# core_3.net
KiCad netlist of a schematic drawn in EAGLE
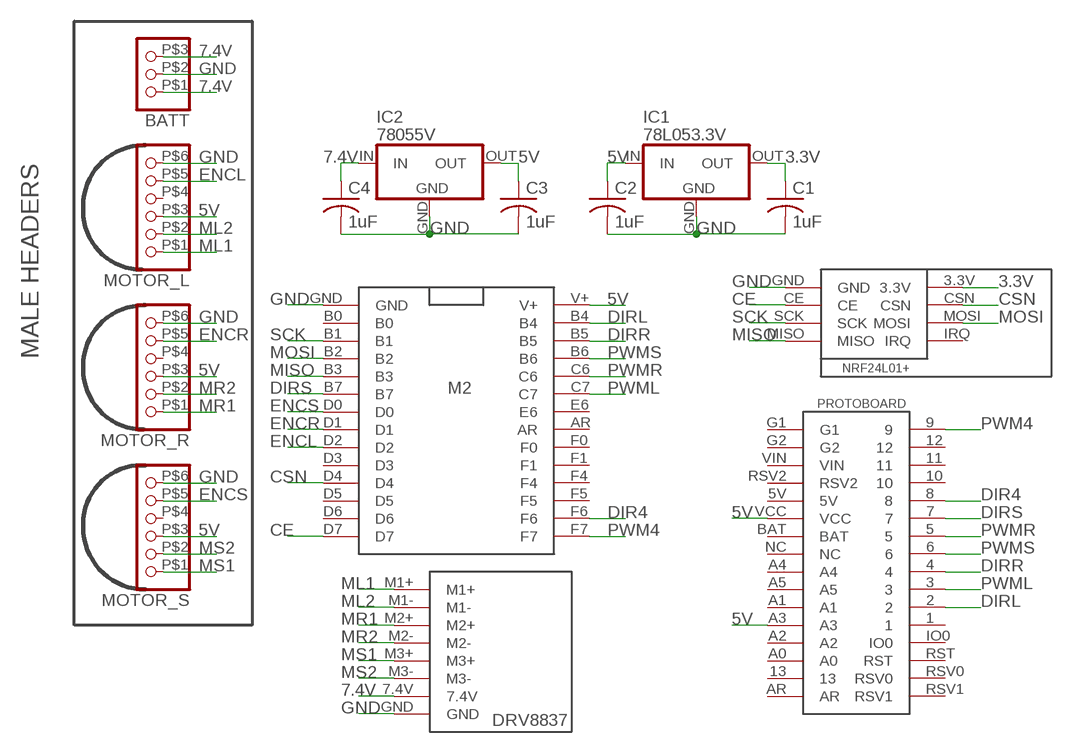
[diagram p0: schematic, sheet 1]

(export (version "E")
  (design (tool "Eeschema 10.0.6"))
  (components
    (comp (ref "BATT")
      (value "PINHD-1X3SMD")
      (footprint "eagle-import:1X3_90SMD")
      (libsource (lib "eagle-import") (part "PINHD-1X3SMD"))
    )
    (comp (ref "C1")
      (value "1uF")
      (footprint "eagle-import:C025-030X050")
      (libsource (lib "eagle-import") (part "C-US025-030X050"))
    )
    (comp (ref "C2")
      (value "1uF")
      (footprint "eagle-import:C025-030X050")
      (libsource (lib "eagle-import") (part "C-US025-030X050"))
    )
    (comp (ref "C3")
      (value "1uF")
      (footprint "eagle-import:C025-030X050")
      (libsource (lib "eagle-import") (part "C-US025-030X050"))
    )
    (comp (ref "C4")
      (value "1uF")
      (footprint "eagle-import:C025-030X050")
      (libsource (lib "eagle-import") (part "C-US025-030X050"))
    )
    (comp (ref "IC1")
      (value "78L053.3V")
      (footprint "eagle-import:TO92")
      (libsource (lib "eagle-import") (part "783.3VL05"))
    )
    (comp (ref "IC2")
      (value "78055V")
      (footprint "eagle-import:TO220H")
      (libsource (lib "eagle-import") (part "785V05"))
    )
    (comp (ref "MOTOR_L")
      (value "PINHD-1X6SMD")
      (footprint "eagle-import:1X6_90SMD")
      (libsource (lib "eagle-import") (part "PINHD-1X6SMD"))
    )
    (comp (ref "MOTOR_R")
      (value "PINHD-1X6SMD")
      (footprint "eagle-import:1X6_90SMD")
      (libsource (lib "eagle-import") (part "PINHD-1X6SMD"))
    )
    (comp (ref "MOTOR_S")
      (value "PINHD-1X6SMD")
      (footprint "eagle-import:1X6_90SMD")
      (libsource (lib "eagle-import") (part "PINHD-1X6SMD"))
    )
    (comp (ref "U$1")
      (value "NRF24L01")
      (footprint "eagle-import:NRF24L01")
      (libsource (lib "eagle-import") (part "NRF24L01"))
    )
    (comp (ref "U$2") (value "M2") (footprint "eagle-import:M2") (libsource (lib "eagle-import") (part "M2")))
    (comp (ref "U$3")
      (value "PROTOBOARDSMD")
      (footprint "eagle-import:PROTOSMD")
      (libsource (lib "eagle-import") (part "PROTOBOARDSMD"))
    )
    (comp (ref "U$4")
      (value "DRV8837")
      (footprint "eagle-import:DRV8837")
      (libsource (lib "eagle-import") (part "DRV8837"))
    )
  )
  (nets
    (net (code "1") (name "/3.3V") (class "Default")
      (node (ref "C1") (pin "1") (pinfunction "1_1") (pintype "passive"))
      (node (ref "IC1") (pin "OUT") (pinfunction "OUT_OUT") (pintype "passive"))
      (node (ref "U$1") (pin "3.3V") (pinfunction "3.3V_3.3V") (pintype "bidirectional"))
    )
    (net (code "2") (name "/5V") (class "Default")
      (node (ref "C2") (pin "1") (pinfunction "1_1") (pintype "passive"))
      (node (ref "C3") (pin "1") (pinfunction "1_1") (pintype "passive"))
      (node (ref "IC1") (pin "IN") (pinfunction "IN_IN") (pintype "input"))
      (node (ref "IC2") (pin "OUT") (pinfunction "OUT_OUT") (pintype "passive"))
      (node (ref "MOTOR_L") (pin "P$3") (pinfunction "3_P$3") (pintype "passive"))
      (node (ref "MOTOR_R") (pin "P$3") (pinfunction "3_P$3") (pintype "passive"))
      (node (ref "MOTOR_S") (pin "P$3") (pinfunction "3_P$3") (pintype "passive"))
      (node (ref "U$2") (pin "V+") (pinfunction "V+_V+") (pintype "bidirectional"))
      (node (ref "U$3") (pin "A3") (pinfunction "A3_A3") (pintype "bidirectional"))
      (node (ref "U$3") (pin "VCC") (pinfunction "VCC_VCC") (pintype "bidirectional"))
    )
    (net (code "3") (name "/7.4V") (class "Default")
      (node (ref "BATT") (pin "P$1") (pinfunction "1_P$1") (pintype "passive"))
      (node (ref "BATT") (pin "P$3") (pinfunction "3_P$3") (pintype "passive"))
      (node (ref "C4") (pin "1") (pinfunction "1_1") (pintype "passive"))
      (node (ref "IC2") (pin "IN") (pinfunction "IN_IN") (pintype "input"))
      (node (ref "U$4") (pin "7.4V") (pinfunction "7.4V_7.4V") (pintype "bidirectional"))
    )
    (net (code "4") (name "/CE") (class "Default")
      (node (ref "U$1") (pin "CE") (pinfunction "CE_CE") (pintype "bidirectional"))
      (node (ref "U$2") (pin "D7") (pinfunction "D7_D7") (pintype "bidirectional"))
    )
    (net (code "5") (name "/CSN") (class "Default")
      (node (ref "U$1") (pin "CSN") (pinfunction "CSN_CSN") (pintype "bidirectional"))
      (node (ref "U$2") (pin "D4") (pinfunction "D4_D4") (pintype "bidirectional"))
    )
    (net (code "6") (name "/DIR4") (class "Default")
      (node (ref "U$2") (pin "F6") (pinfunction "F6_F6") (pintype "bidirectional"))
      (node (ref "U$3") (pin "8") (pinfunction "8_8") (pintype "bidirectional"))
    )
    (net (code "7") (name "/DIRL") (class "Default")
      (node (ref "U$2") (pin "B4") (pinfunction "B4_B4") (pintype "bidirectional"))
      (node (ref "U$3") (pin "2") (pinfunction "2_2") (pintype "bidirectional"))
    )
    (net (code "8") (name "/DIRR") (class "Default")
      (node (ref "U$2") (pin "B5") (pinfunction "B5_B5") (pintype "bidirectional"))
      (node (ref "U$3") (pin "4") (pinfunction "4_4") (pintype "bidirectional"))
    )
    (net (code "9") (name "/DIRS") (class "Default")
      (node (ref "U$2") (pin "B7") (pinfunction "B7_B7") (pintype "bidirectional"))
      (node (ref "U$3") (pin "7") (pinfunction "7_7") (pintype "bidirectional"))
    )
    (net (code "10") (name "/ENCL") (class "Default")
      (node (ref "MOTOR_L") (pin "P$5") (pinfunction "5_P$5") (pintype "passive"))
      (node (ref "U$2") (pin "D2") (pinfunction "D2_D2") (pintype "bidirectional"))
    )
    (net (code "11") (name "/ENCR") (class "Default")
      (node (ref "MOTOR_R") (pin "P$5") (pinfunction "5_P$5") (pintype "passive"))
      (node (ref "U$2") (pin "D1") (pinfunction "D1_D1") (pintype "bidirectional"))
    )
    (net (code "12") (name "/ENCS") (class "Default")
      (node (ref "MOTOR_S") (pin "P$5") (pinfunction "5_P$5") (pintype "passive"))
      (node (ref "U$2") (pin "D0") (pinfunction "D0_D0") (pintype "bidirectional"))
    )
    (net (code "13") (name "/GND") (class "Default")
      (node (ref "BATT") (pin "P$2") (pinfunction "2_P$2") (pintype "passive"))
      (node (ref "C1") (pin "2") (pinfunction "2_2") (pintype "passive"))
      (node (ref "C2") (pin "2") (pinfunction "2_2") (pintype "passive"))
      (node (ref "C3") (pin "2") (pinfunction "2_2") (pintype "passive"))
      (node (ref "C4") (pin "2") (pinfunction "2_2") (pintype "passive"))
      (node (ref "IC1") (pin "GND") (pinfunction "GND_GND") (pintype "passive"))
      (node (ref "IC2") (pin "GND") (pinfunction "GND_GND") (pintype "passive"))
      (node (ref "MOTOR_L") (pin "P$6") (pinfunction "6_P$6") (pintype "passive"))
      (node (ref "MOTOR_R") (pin "P$6") (pinfunction "6_P$6") (pintype "passive"))
      (node (ref "MOTOR_S") (pin "P$6") (pinfunction "6_P$6") (pintype "passive"))
      (node (ref "U$1") (pin "GND") (pinfunction "GND_GND") (pintype "bidirectional"))
      (node (ref "U$2") (pin "GND") (pinfunction "GND_GND") (pintype "bidirectional"))
      (node (ref "U$4") (pin "GND") (pinfunction "GND_GND") (pintype "bidirectional"))
    )
    (net (code "14") (name "/MISO") (class "Default")
      (node (ref "U$1") (pin "MISO") (pinfunction "MISO_MISO") (pintype "bidirectional"))
      (node (ref "U$2") (pin "B3") (pinfunction "B3_B3") (pintype "bidirectional"))
    )
    (net (code "15") (name "/ML1") (class "Default")
      (node (ref "MOTOR_L") (pin "P$1") (pinfunction "1_P$1") (pintype "passive"))
      (node (ref "U$4") (pin "M1+") (pinfunction "M1+_M1+") (pintype "bidirectional"))
    )
    (net (code "16") (name "/ML2") (class "Default")
      (node (ref "MOTOR_L") (pin "P$2") (pinfunction "2_P$2") (pintype "passive"))
      (node (ref "U$4") (pin "M1-") (pinfunction "M1-_M1-") (pintype "bidirectional"))
    )
    (net (code "17") (name "/MOSI") (class "Default")
      (node (ref "U$1") (pin "MOSI") (pinfunction "MOSI_MOSI") (pintype "bidirectional"))
      (node (ref "U$2") (pin "B2") (pinfunction "B2_B2") (pintype "bidirectional"))
    )
    (net (code "18") (name "/MR1") (class "Default")
      (node (ref "MOTOR_R") (pin "P$1") (pinfunction "1_P$1") (pintype "passive"))
      (node (ref "U$4") (pin "M2+") (pinfunction "M2+_M2+") (pintype "bidirectional"))
    )
    (net (code "19") (name "/MR2") (class "Default")
      (node (ref "MOTOR_R") (pin "P$2") (pinfunction "2_P$2") (pintype "passive"))
      (node (ref "U$4") (pin "M2-") (pinfunction "M2-_M2-") (pintype "bidirectional"))
    )
    (net (code "20") (name "/MS1") (class "Default")
      (node (ref "MOTOR_S") (pin "P$1") (pinfunction "1_P$1") (pintype "passive"))
      (node (ref "U$4") (pin "M3+") (pinfunction "M3+_M3+") (pintype "bidirectional"))
    )
    (net (code "21") (name "/MS2") (class "Default")
      (node (ref "MOTOR_S") (pin "P$2") (pinfunction "2_P$2") (pintype "passive"))
      (node (ref "U$4") (pin "M3-") (pinfunction "M3-_M3-") (pintype "bidirectional"))
    )
    (net (code "22") (name "/PWM4") (class "Default")
      (node (ref "U$2") (pin "F7") (pinfunction "F7_F7") (pintype "bidirectional"))
      (node (ref "U$3") (pin "9") (pinfunction "9_9") (pintype "bidirectional"))
    )
    (net (code "23") (name "/PWML") (class "Default")
      (node (ref "U$2") (pin "C7") (pinfunction "C7_C7") (pintype "bidirectional"))
      (node (ref "U$3") (pin "3") (pinfunction "3_3") (pintype "bidirectional"))
    )
    (net (code "24") (name "/PWMR") (class "Default")
      (node (ref "U$2") (pin "C6") (pinfunction "C6_C6") (pintype "bidirectional"))
      (node (ref "U$3") (pin "5") (pinfunction "5_5") (pintype "bidirectional"))
    )
    (net (code "25") (name "/PWMS") (class "Default")
      (node (ref "U$2") (pin "B6") (pinfunction "B6_B6") (pintype "bidirectional"))
      (node (ref "U$3") (pin "6") (pinfunction "6_6") (pintype "bidirectional"))
    )
    (net (code "26") (name "/SCK") (class "Default")
      (node (ref "U$1") (pin "SCK") (pinfunction "SCK_SCK") (pintype "bidirectional"))
      (node (ref "U$2") (pin "B1") (pinfunction "B1_B1") (pintype "bidirectional"))
    )
    (net (code "27") (name "unconnected-(MOTOR_L-4-PadP$4)") (class "Default")
      (node (ref "MOTOR_L") (pin "P$4") (pinfunction "4_P$4") (pintype "passive"))
    )
    (net (code "28") (name "unconnected-(MOTOR_R-4-PadP$4)") (class "Default")
      (node (ref "MOTOR_R") (pin "P$4") (pinfunction "4_P$4") (pintype "passive"))
    )
    (net (code "29") (name "unconnected-(MOTOR_S-4-PadP$4)") (class "Default")
      (node (ref "MOTOR_S") (pin "P$4") (pinfunction "4_P$4") (pintype "passive"))
    )
    (net (code "30") (name "unconnected-(U$1-PadIRQ)") (class "Default")
      (node (ref "U$1") (pin "IRQ") (pinfunction "IRQ_IRQ") (pintype "bidirectional"))
    )
    (net (code "31") (name "unconnected-(U$2-PadAR)") (class "Default")
      (node (ref "U$2") (pin "AR") (pinfunction "AR_AR") (pintype "bidirectional"))
    )
    (net (code "32") (name "unconnected-(U$2-PadB0)") (class "Default")
      (node (ref "U$2") (pin "B0") (pinfunction "B0_B0") (pintype "bidirectional"))
    )
    (net (code "33") (name "unconnected-(U$2-PadD3)") (class "Default")
      (node (ref "U$2") (pin "D3") (pinfunction "D3_D3") (pintype "bidirectional"))
    )
    (net (code "34") (name "unconnected-(U$2-PadD5)") (class "Default")
      (node (ref "U$2") (pin "D5") (pinfunction "D5_D5") (pintype "bidirectional"))
    )
    (net (code "35") (name "unconnected-(U$2-PadD6)") (class "Default")
      (node (ref "U$2") (pin "D6") (pinfunction "D6_D6") (pintype "bidirectional"))
    )
    (net (code "36") (name "unconnected-(U$2-PadE6)") (class "Default")
      (node (ref "U$2") (pin "E6") (pinfunction "E6_E6") (pintype "bidirectional"))
    )
    (net (code "37") (name "unconnected-(U$2-PadF0)") (class "Default")
      (node (ref "U$2") (pin "F0") (pinfunction "F0_F0") (pintype "bidirectional"))
    )
    (net (code "38") (name "unconnected-(U$2-PadF1)") (class "Default")
      (node (ref "U$2") (pin "F1") (pinfunction "F1_F1") (pintype "bidirectional"))
    )
    (net (code "39") (name "unconnected-(U$2-PadF4)") (class "Default")
      (node (ref "U$2") (pin "F4") (pinfunction "F4_F4") (pintype "bidirectional"))
    )
    (net (code "40") (name "unconnected-(U$2-PadF5)") (class "Default")
      (node (ref "U$2") (pin "F5") (pinfunction "F5_F5") (pintype "bidirectional"))
    )
    (net (code "41") (name "unconnected-(U$3-Pad1)") (class "Default")
      (node (ref "U$3") (pin "1") (pinfunction "1_1") (pintype "bidirectional"))
    )
    (net (code "42") (name "unconnected-(U$3-Pad5V)") (class "Default")
      (node (ref "U$3") (pin "5V") (pinfunction "5V_5V") (pintype "bidirectional"))
    )
    (net (code "43") (name "unconnected-(U$3-Pad10)") (class "Default")
      (node (ref "U$3") (pin "10") (pinfunction "10_10") (pintype "bidirectional"))
    )
    (net (code "44") (name "unconnected-(U$3-Pad11)") (class "Default")
      (node (ref "U$3") (pin "11") (pinfunction "11_11") (pintype "bidirectional"))
    )
    (net (code "45") (name "unconnected-(U$3-Pad12)") (class "Default")
      (node (ref "U$3") (pin "12") (pinfunction "12_12") (pintype "bidirectional"))
    )
    (net (code "46") (name "unconnected-(U$3-Pad13)") (class "Default")
      (node (ref "U$3") (pin "13") (pinfunction "13_13") (pintype "bidirectional"))
    )
    (net (code "47") (name "unconnected-(U$3-PadA0)") (class "Default")
      (node (ref "U$3") (pin "A0") (pinfunction "A0_A0") (pintype "bidirectional"))
    )
    (net (code "48") (name "unconnected-(U$3-PadA1)") (class "Default")
      (node (ref "U$3") (pin "A1") (pinfunction "A1_A1") (pintype "bidirectional"))
    )
    (net (code "49") (name "unconnected-(U$3-PadA2)") (class "Default")
      (node (ref "U$3") (pin "A2") (pinfunction "A2_A2") (pintype "bidirectional"))
    )
    (net (code "50") (name "unconnected-(U$3-PadA4)") (class "Default")
      (node (ref "U$3") (pin "A4") (pinfunction "A4_A4") (pintype "bidirectional"))
    )
    (net (code "51") (name "unconnected-(U$3-PadA5)") (class "Default")
      (node (ref "U$3") (pin "A5") (pinfunction "A5_A5") (pintype "bidirectional"))
    )
    (net (code "52") (name "unconnected-(U$3-PadAR)") (class "Default")
      (node (ref "U$3") (pin "AR") (pinfunction "AR_AR") (pintype "bidirectional"))
    )
    (net (code "53") (name "unconnected-(U$3-PadBAT)") (class "Default")
      (node (ref "U$3") (pin "BAT") (pinfunction "BAT_BAT") (pintype "bidirectional"))
    )
    (net (code "54") (name "unconnected-(U$3-PadG1)") (class "Default")
      (node (ref "U$3") (pin "G1") (pinfunction "G1_G1") (pintype "bidirectional"))
    )
    (net (code "55") (name "unconnected-(U$3-PadG2)") (class "Default")
      (node (ref "U$3") (pin "G2") (pinfunction "G2_G2") (pintype "bidirectional"))
    )
    (net (code "56") (name "unconnected-(U$3-PadIO0)") (class "Default")
      (node (ref "U$3") (pin "IO0") (pinfunction "IO0_IO0") (pintype "bidirectional"))
    )
    (net (code "57") (name "unconnected-(U$3-PadNC)") (class "Default")
      (node (ref "U$3") (pin "NC") (pinfunction "NC_NC") (pintype "bidirectional"))
    )
    (net (code "58") (name "unconnected-(U$3-PadRST)") (class "Default")
      (node (ref "U$3") (pin "RST") (pinfunction "RST_RST") (pintype "bidirectional"))
    )
    (net (code "59") (name "unconnected-(U$3-PadRSV0)") (class "Default")
      (node (ref "U$3") (pin "RSV0") (pinfunction "RSV0_RSV0") (pintype "bidirectional"))
    )
    (net (code "60") (name "unconnected-(U$3-PadRSV1)") (class "Default")
      (node (ref "U$3") (pin "RSV1") (pinfunction "RSV1_RSV1") (pintype "bidirectional"))
    )
    (net (code "61") (name "unconnected-(U$3-PadRSV2)") (class "Default")
      (node (ref "U$3") (pin "RSV2") (pinfunction "RSV2_RSV2") (pintype "bidirectional"))
    )
    (net (code "62") (name "unconnected-(U$3-PadVIN)") (class "Default")
      (node (ref "U$3") (pin "VIN") (pinfunction "VIN_VIN") (pintype "bidirectional"))
    )
  )
)
